# MCP9808_breakout.net
KiCad netlist of a schematic drawn in EAGLE
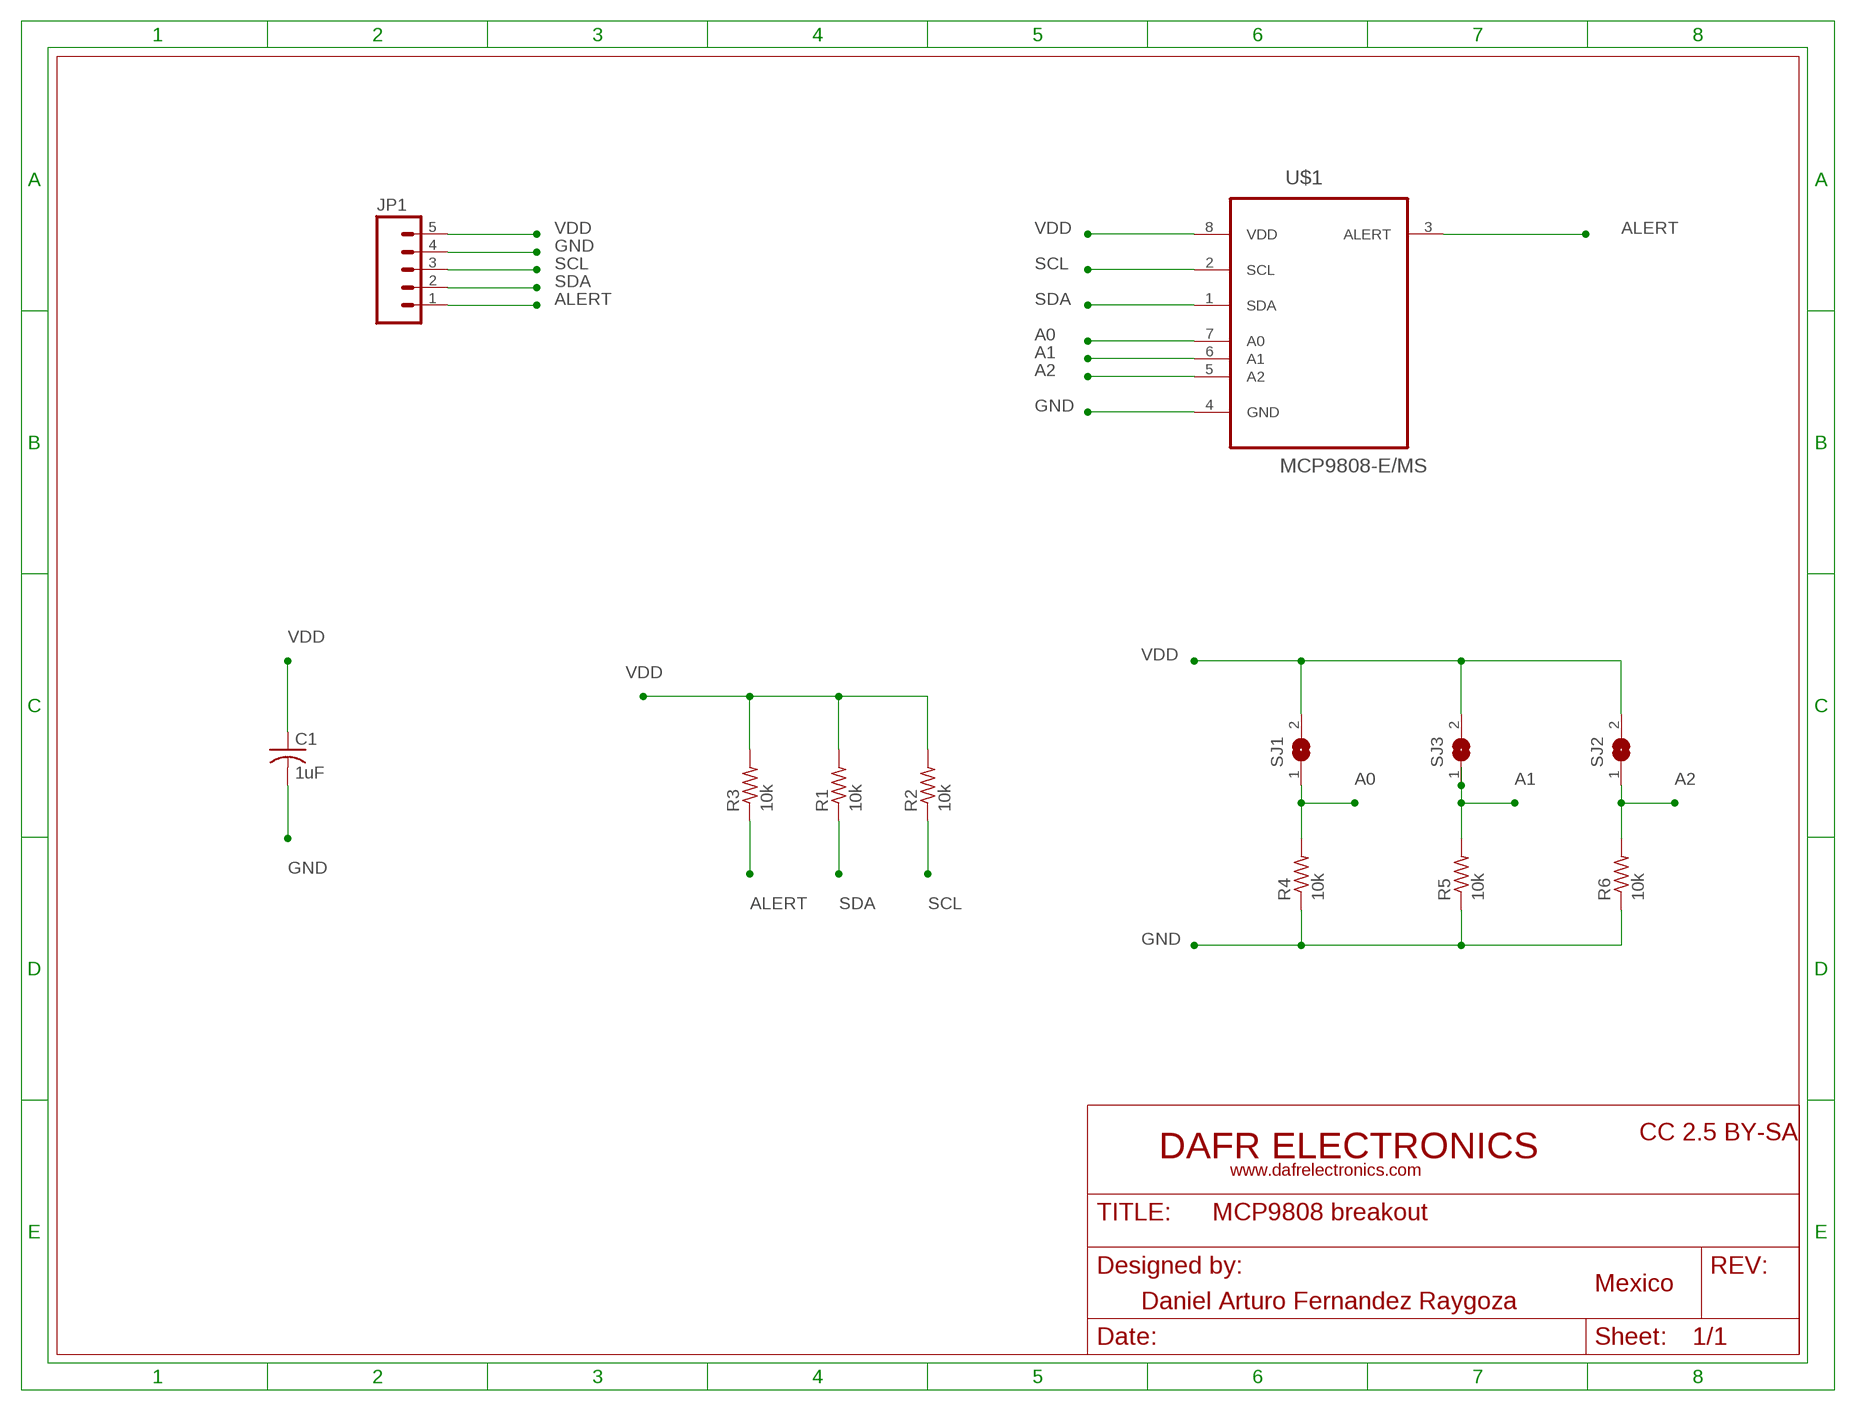
[diagram p0: schematic, sheet 1]

(export (version "E")
  (design (tool "Eeschema 10.0.6"))
  (components
    (comp (ref "C1")
      (value "1uF")
      (footprint "eagle-import:C0603K")
      (libsource (lib "eagle-import") (part "C-USC0603K"))
    )
    (comp (ref "JP1")
      (value "M05NO_SILK")
      (footprint "eagle-import:1X05_NO_SILK")
      (libsource (lib "eagle-import") (part "M05NO_SILK"))
    )
    (comp (ref "R1")
      (value "10k")
      (footprint "eagle-import:R0805")
      (libsource (lib "eagle-import") (part "R-US_R0805"))
    )
    (comp (ref "R2")
      (value "10k")
      (footprint "eagle-import:R0805")
      (libsource (lib "eagle-import") (part "R-US_R0805"))
    )
    (comp (ref "R3")
      (value "10k")
      (footprint "eagle-import:R0805")
      (libsource (lib "eagle-import") (part "R-US_R0805"))
    )
    (comp (ref "R4")
      (value "10k")
      (footprint "eagle-import:R0805")
      (libsource (lib "eagle-import") (part "R-US_R0805"))
    )
    (comp (ref "R5")
      (value "10k")
      (footprint "eagle-import:R0805")
      (libsource (lib "eagle-import") (part "R-US_R0805"))
    )
    (comp (ref "R6")
      (value "10k")
      (footprint "eagle-import:R0805")
      (libsource (lib "eagle-import") (part "R-US_R0805"))
    )
    (comp (ref "SJ1") (value "SJ") (footprint "eagle-import:SJ") (libsource (lib "eagle-import") (part "SJ")))
    (comp (ref "SJ2") (value "SJ") (footprint "eagle-import:SJ") (libsource (lib "eagle-import") (part "SJ")))
    (comp (ref "SJ3") (value "SJ") (footprint "eagle-import:SJ") (libsource (lib "eagle-import") (part "SJ")))
    (comp (ref "U$1")
      (value "MCP9808-E/MS")
      (footprint "eagle-import:SOP65P490X110-8N")
      (libsource (lib "eagle-import") (part "MCP9808-E/MS"))
    )
  )
  (nets
    (net (code "1") (name "/A0") (class "Default")
      (node (ref "R4") (pin "2") (pinfunction "2_2") (pintype "passive"))
      (node (ref "SJ1") (pin "1") (pinfunction "1_1") (pintype "passive"))
      (node (ref "U$1") (pin "7") (pinfunction "A0_7") (pintype "input"))
    )
    (net (code "2") (name "/A1") (class "Default")
      (node (ref "R5") (pin "2") (pinfunction "2_2") (pintype "passive"))
      (node (ref "SJ3") (pin "1") (pinfunction "1_1") (pintype "passive"))
      (node (ref "U$1") (pin "6") (pinfunction "A1_6") (pintype "input"))
    )
    (net (code "3") (name "/A2") (class "Default")
      (node (ref "R6") (pin "2") (pinfunction "2_2") (pintype "passive"))
      (node (ref "SJ2") (pin "1") (pinfunction "1_1") (pintype "passive"))
      (node (ref "U$1") (pin "5") (pinfunction "A2_5") (pintype "input"))
    )
    (net (code "4") (name "/ALERT") (class "Default")
      (node (ref "JP1") (pin "1") (pinfunction "1_1") (pintype "passive"))
      (node (ref "R3") (pin "1") (pinfunction "1_1") (pintype "passive"))
      (node (ref "U$1") (pin "3") (pinfunction "ALERT_3") (pintype "output"))
    )
    (net (code "5") (name "/GND") (class "Default")
      (node (ref "C1") (pin "2") (pinfunction "2_2") (pintype "passive"))
      (node (ref "JP1") (pin "4") (pinfunction "4_4") (pintype "passive"))
      (node (ref "R4") (pin "1") (pinfunction "1_1") (pintype "passive"))
      (node (ref "R5") (pin "1") (pinfunction "1_1") (pintype "passive"))
      (node (ref "R6") (pin "1") (pinfunction "1_1") (pintype "passive"))
      (node (ref "U$1") (pin "4") (pinfunction "GND_4") (pintype "passive"))
    )
    (net (code "6") (name "/SCL") (class "Default")
      (node (ref "JP1") (pin "3") (pinfunction "3_3") (pintype "passive"))
      (node (ref "R2") (pin "1") (pinfunction "1_1") (pintype "passive"))
      (node (ref "U$1") (pin "2") (pinfunction "SCL_2") (pintype "input"))
    )
    (net (code "7") (name "/SDA") (class "Default")
      (node (ref "JP1") (pin "2") (pinfunction "2_2") (pintype "passive"))
      (node (ref "R1") (pin "1") (pinfunction "1_1") (pintype "passive"))
      (node (ref "U$1") (pin "1") (pinfunction "SDA_1") (pintype "bidirectional"))
    )
    (net (code "8") (name "/VDD") (class "Default")
      (node (ref "C1") (pin "1") (pinfunction "1_1") (pintype "passive"))
      (node (ref "JP1") (pin "5") (pinfunction "5_5") (pintype "passive"))
      (node (ref "R1") (pin "2") (pinfunction "2_2") (pintype "passive"))
      (node (ref "R2") (pin "2") (pinfunction "2_2") (pintype "passive"))
      (node (ref "R3") (pin "2") (pinfunction "2_2") (pintype "passive"))
      (node (ref "SJ1") (pin "2") (pinfunction "2_2") (pintype "passive"))
      (node (ref "SJ2") (pin "2") (pinfunction "2_2") (pintype "passive"))
      (node (ref "SJ3") (pin "2") (pinfunction "2_2") (pintype "passive"))
      (node (ref "U$1") (pin "8") (pinfunction "VDD_8") (pintype "power_in"))
    )
  )
)
